# fa3d_Dock_NEW_Small.net
KiCad netlist of a schematic drawn in EAGLE
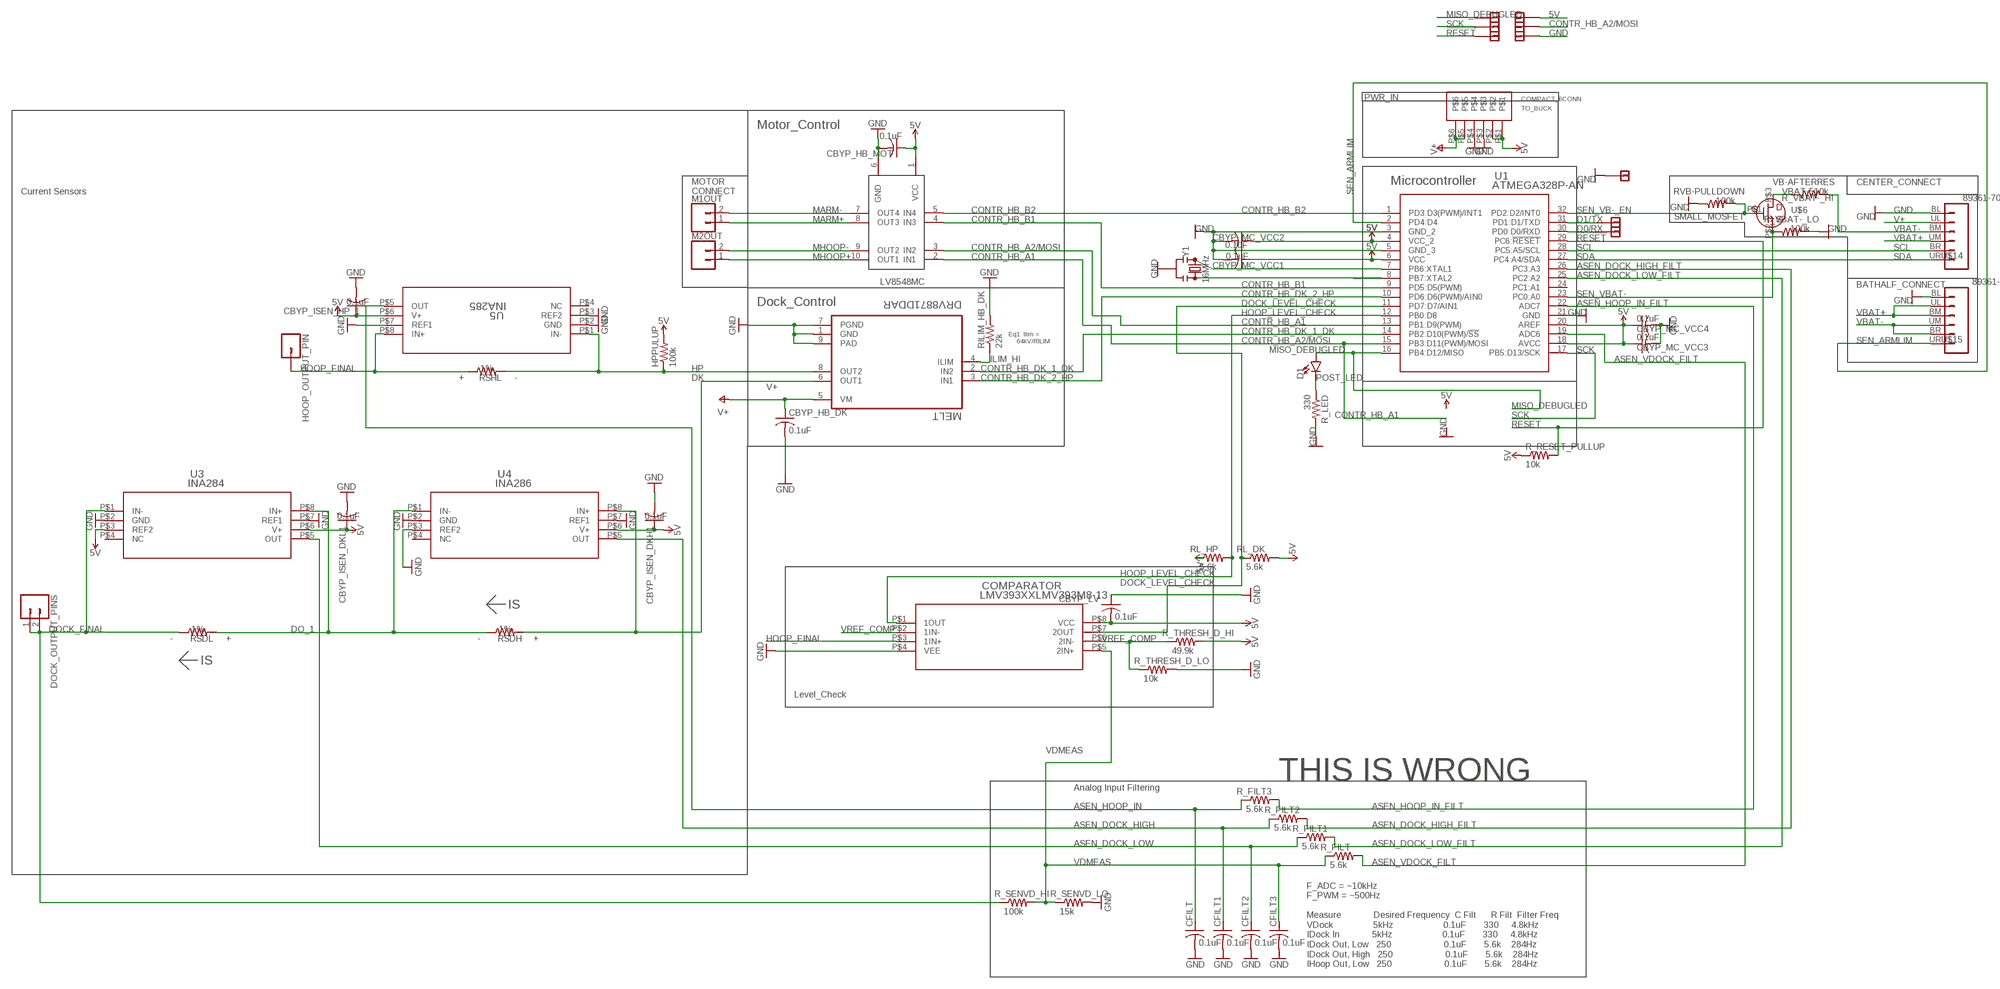
[diagram p0: schematic, sheet 1, part 1 of 2]
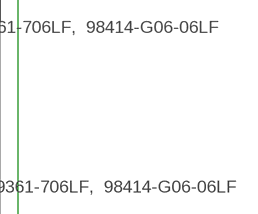
[diagram p1: schematic, sheet 1, part 2 of 2]

(export (version "E")
  (design (tool "Eeschema 10.0.6"))
  (components
    (comp (ref "CBYP_HB_DK")
      (value "0.1uF")
      (footprint "eagle-import:C0603")
      (fields (field (name "PARTNO") "CL10B104KB8NNNC"))
      (libsource (lib "eagle-import") (part "C-USC0603"))
    )
    (comp (ref "CBYP_HB_MOT")
      (value "0.1uF")
      (footprint "eagle-import:C0402")
      (fields (field (name "PARTNO") "885012105010"))
      (libsource (lib "eagle-import") (part "C-USC0402"))
    )
    (comp (ref "CBYP_ISEN_DKH1")
      (value "0.1uF")
      (footprint "eagle-import:C0402")
      (fields (field (name "PARTNO") "885012105010"))
      (libsource (lib "eagle-import") (part "C-USC0402"))
    )
    (comp (ref "CBYP_ISEN_DKL1")
      (value "0.1uF")
      (footprint "eagle-import:C0402")
      (fields (field (name "PARTNO") "885012105010"))
      (libsource (lib "eagle-import") (part "C-USC0402"))
    )
    (comp (ref "CBYP_ISEN_HP_1")
      (value "0.1uF")
      (footprint "eagle-import:C0402")
      (fields (field (name "PARTNO") "885012105010"))
      (libsource (lib "eagle-import") (part "C-USC0402"))
    )
    (comp (ref "CBYP_LV")
      (value "0.1uF")
      (footprint "eagle-import:C0402")
      (fields (field (name "PARTNO") "885012105010"))
      (libsource (lib "eagle-import") (part "C-USC0402"))
    )
    (comp (ref "CBYP_MC_VCC1")
      (value "0.1uF")
      (footprint "eagle-import:C0402")
      (fields (field (name "PARTNO") "885012105010"))
      (libsource (lib "eagle-import") (part "C-USC0402"))
    )
    (comp (ref "CBYP_MC_VCC2")
      (value "0.1uF")
      (footprint "eagle-import:C0402")
      (fields (field (name "PARTNO") "885012105010"))
      (libsource (lib "eagle-import") (part "C-USC0402"))
    )
    (comp (ref "CBYP_MC_VCC3")
      (value "0.1uF")
      (footprint "eagle-import:C0402")
      (fields (field (name "PARTNO") "885012105010"))
      (libsource (lib "eagle-import") (part "C-USC0402"))
    )
    (comp (ref "CBYP_MC_VCC4")
      (value "0.1uF")
      (footprint "eagle-import:C0402")
      (fields (field (name "PARTNO") "885012105010"))
      (libsource (lib "eagle-import") (part "C-USC0402"))
    )
    (comp (ref "CFILT")
      (value "0.1uF")
      (footprint "eagle-import:C0402")
      (fields (field (name "PARTNO") "885012105010"))
      (libsource (lib "eagle-import") (part "C-USC0402"))
    )
    (comp (ref "CFILT1")
      (value "0.1uF")
      (footprint "eagle-import:C0402")
      (fields (field (name "PARTNO") "885012105010"))
      (libsource (lib "eagle-import") (part "C-USC0402"))
    )
    (comp (ref "CFILT2")
      (value "0.1uF")
      (footprint "eagle-import:C0402")
      (fields (field (name "PARTNO") "885012105010"))
      (libsource (lib "eagle-import") (part "C-USC0402"))
    )
    (comp (ref "CFILT3")
      (value "0.1uF")
      (footprint "eagle-import:C0402")
      (fields (field (name "PARTNO") "885012105010"))
      (libsource (lib "eagle-import") (part "C-USC0402"))
    )
    (comp (ref "COMPARATOR")
      (value "LMV393XXLMV393M8-13")
      (footprint "eagle-import:MSOP-8")
      (fields (field (name "PARTNO") "LMV393M8-13"))
      (libsource (lib "eagle-import") (part "LMV393XXLMV393M8-13"))
    )
    (comp (ref "D1")
      (value "LED0603")
      (footprint "eagle-import:LED-0603")
      (fields (field (name "PARTNO") "SML-D12U1WT86"))
      (libsource (lib "eagle-import") (part "LED0603"))
    )
    (comp (ref "DOCK_OUTPUT_PINS")
      (value "CONN_02")
      (footprint "eagle-import:1X02")
      (libsource (lib "eagle-import") (part "CONN_02"))
    )
    (comp (ref "HOOP_OUTPUT_PIN")
      (value "CONN_01")
      (footprint "eagle-import:1X01")
      (libsource (lib "eagle-import") (part "CONN_01"))
    )
    (comp (ref "HPPULUP")
      (value "100k")
      (footprint "eagle-import:R0402")
      (fields (field (name "PARTNO") "RMCF0402JT100K"))
      (libsource (lib "eagle-import") (part "R-US_R0402"))
    )
    (comp (ref "M1OUT")
      (value "CONN_02")
      (footprint "eagle-import:1X02")
      (libsource (lib "eagle-import") (part "CONN_02"))
    )
    (comp (ref "M2OUT")
      (value "CONN_02")
      (footprint "eagle-import:1X02")
      (libsource (lib "eagle-import") (part "CONN_02"))
    )
    (comp (ref "MELT")
      (value "DRV8871DDAR")
      (footprint "eagle-import:SOIC127P600X170-8N")
      (fields (field (name "DIGI-KEY_PART_NUMBER") "296-43024-1-ND") (field (name "MF") "Texas Instruments"))
      (libsource (lib "eagle-import") (part "DRV8871DDAR"))
    )
    (comp (ref "MOTOR")
      (value "LV8548MC-AH")
      (footprint "eagle-import:10-SOP")
      (libsource (lib "eagle-import") (part "LV8548MC-AH"))
    )
    (comp (ref "RILIM_HB_DK")
      (value "22k")
      (footprint "eagle-import:R0603")
      (fields (field (name "PARTNO") "RMCF0402JT22K0"))
      (libsource (lib "eagle-import") (part "R-US_R0603"))
    )
    (comp (ref "RL_DK")
      (value "5.6k")
      (footprint "eagle-import:R0402")
      (fields (field (name "PARTNO") "CRGCQ0402F5K6"))
      (libsource (lib "eagle-import") (part "R-US_R0402"))
    )
    (comp (ref "RL_HP")
      (value "5.6k")
      (footprint "eagle-import:R0402")
      (fields (field (name "PARTNO") "CRGCQ0402F5K6"))
      (libsource (lib "eagle-import") (part "R-US_R0402"))
    )
    (comp (ref "RSDH")
      (value "25m")
      (footprint "eagle-import:R0603")
      (fields (field (name "PARTNO") "ERJ-3BWFR025V") (field (name "SIZE") "1206") (field (name "TOL") "1%"))
      (libsource (lib "eagle-import") (part "R-US_R0603"))
    )
    (comp (ref "RSDL")
      (value "25m")
      (footprint "eagle-import:R0603")
      (fields (field (name "PARTNO") "ERJ-3BWFR025V") (field (name "SIZE") "1206") (field (name "TOL") "1%"))
      (libsource (lib "eagle-import") (part "R-US_R0603"))
    )
    (comp (ref "RSHL")
      (value "25m")
      (footprint "eagle-import:R0603")
      (fields (field (name "PARTNO") "ERJ-3BWFR025V") (field (name "SIZE") "1206") (field (name "TOL") "1%"))
      (libsource (lib "eagle-import") (part "R-US_R0603"))
    )
    (comp (ref "RVB-PULLDOWN")
      (value "100k")
      (footprint "eagle-import:R0402")
      (fields (field (name "PARTNO") "RMCF0402JT100K"))
      (libsource (lib "eagle-import") (part "R-US_R0402"))
    )
    (comp (ref "R_FILT")
      (value "5.6k")
      (footprint "eagle-import:R0402")
      (fields (field (name "PARTNO") "CRGCQ0402F5K6"))
      (libsource (lib "eagle-import") (part "R-US_R0402"))
    )
    (comp (ref "R_FILT1")
      (value "5.6k")
      (footprint "eagle-import:R0402")
      (fields (field (name "PARTNO") "CRGCQ0402F5K6"))
      (libsource (lib "eagle-import") (part "R-US_R0402"))
    )
    (comp (ref "R_FILT2")
      (value "5.6k")
      (footprint "eagle-import:R0402")
      (fields (field (name "PARTNO") "CRGCQ0402F5K6"))
      (libsource (lib "eagle-import") (part "R-US_R0402"))
    )
    (comp (ref "R_FILT3")
      (value "5.6k")
      (footprint "eagle-import:R0402")
      (fields (field (name "PARTNO") "CRGCQ0402F5K6"))
      (libsource (lib "eagle-import") (part "R-US_R0402"))
    )
    (comp (ref "R_LED")
      (value "330")
      (footprint "eagle-import:R0402")
      (fields (field (name "PARTNO") "RMCF0402JT330R"))
      (libsource (lib "eagle-import") (part "R-US_R0402"))
    )
    (comp (ref "R_RESET_PULLUP")
      (value "10k")
      (footprint "eagle-import:R0402")
      (fields (field (name "PARTNO") "RR0510P-103-D"))
      (libsource (lib "eagle-import") (part "R-US_R0402"))
    )
    (comp (ref "R_SENVD_HI")
      (value "100k")
      (footprint "eagle-import:R0402")
      (fields (field (name "PARTNO") "RMCF0402JT100K"))
      (libsource (lib "eagle-import") (part "R-US_R0402"))
    )
    (comp (ref "R_SENVD_LO")
      (value "15k")
      (footprint "eagle-import:R0402")
      (fields (field (name "PARTNO") "RMCF0402JT15K0"))
      (libsource (lib "eagle-import") (part "R-US_R0402"))
    )
    (comp (ref "R_THRESH_D_HI")
      (value "49.9k")
      (footprint "eagle-import:R0402")
      (fields (field (name "PARTNO") "RMCF0402FT49K9"))
      (libsource (lib "eagle-import") (part "R-US_R0402"))
    )
    (comp (ref "R_THRESH_D_LO")
      (value "10k")
      (footprint "eagle-import:R0402")
      (fields (field (name "PARTNO") "RR0510P-103-D"))
      (libsource (lib "eagle-import") (part "R-US_R0402"))
    )
    (comp (ref "R_VBAT-_HI")
      (value "510k")
      (footprint "eagle-import:R0402")
      (fields (field (name "PARTNO") "RMCF0402JT510K"))
      (libsource (lib "eagle-import") (part "R-US_R0402"))
    )
    (comp (ref "R_VBAT-_LO")
      (value "100k")
      (footprint "eagle-import:R0402")
      (fields (field (name "PARTNO") "RMCF0402JT100K"))
      (libsource (lib "eagle-import") (part "R-US_R0402"))
    )
    (comp (ref "TO_BUCK")
      (value "COMPACT_6CONN")
      (footprint "eagle-import:COMPACT_6CONN")
      (libsource (lib "eagle-import") (part "COMPACT_6CONN"))
    )
    (comp (ref "U$1")
      (value "SIMPLE_VIA_CONNECTION")
      (footprint "eagle-import:SIMPLEVIA")
      (libsource (lib "eagle-import") (part "SIMPLE_VIA_CONNECTION"))
    )
    (comp (ref "U$2")
      (value "SIMPLE_VIA_CONNECTION")
      (footprint "eagle-import:SIMPLEVIA")
      (libsource (lib "eagle-import") (part "SIMPLE_VIA_CONNECTION"))
    )
    (comp (ref "U$3")
      (value "SIMPLE_VIA_CONNECTION")
      (footprint "eagle-import:SIMPLEVIA")
      (libsource (lib "eagle-import") (part "SIMPLE_VIA_CONNECTION"))
    )
    (comp (ref "U$4")
      (value "SIMPLE_VIA_CONNECTION")
      (footprint "eagle-import:SIMPLEVIA")
      (libsource (lib "eagle-import") (part "SIMPLE_VIA_CONNECTION"))
    )
    (comp (ref "U$5")
      (value "SIMPLE_VIA_CONNECTION")
      (footprint "eagle-import:SIMPLEVIA")
      (libsource (lib "eagle-import") (part "SIMPLE_VIA_CONNECTION"))
    )
    (comp (ref "U$6")
      (value "SMALL_MOSFET")
      (footprint "eagle-import:SOT-23")
      (fields (field (name "PARTNO") "BSS138"))
      (libsource (lib "eagle-import") (part "SMALL_MOSFET"))
    )
    (comp (ref "U$7")
      (value "SIMPLE_VIA_CONNECTION")
      (footprint "eagle-import:SIMPLEVIA")
      (libsource (lib "eagle-import") (part "SIMPLE_VIA_CONNECTION"))
    )
    (comp (ref "U$8")
      (value "SIMPLE_VIA_CONNECTION")
      (footprint "eagle-import:SIMPLEVIA")
      (libsource (lib "eagle-import") (part "SIMPLE_VIA_CONNECTION"))
    )
    (comp (ref "U$9")
      (value "SIMPLE_VIA_CONNECTION")
      (footprint "eagle-import:SIMPLEVIA")
      (libsource (lib "eagle-import") (part "SIMPLE_VIA_CONNECTION"))
    )
    (comp (ref "U$10")
      (value "SIMPLE_VIA_CONNECTION")
      (footprint "eagle-import:SIMPLEVIA")
      (libsource (lib "eagle-import") (part "SIMPLE_VIA_CONNECTION"))
    )
    (comp (ref "U$14")
      (value "89361-706LF, 98414-G06-06LF")
      (footprint "eagle-import:2X3_2MMPITCH")
      (fields (field (name "PARTNO") "98414-G06-06LF"))
      (libsource (lib "eagle-import") (part "CONNECTORHEADERTHROUGHHOLE6POSITION0.079{dblquote}(2.00MM)"))
    )
    (comp (ref "U$15")
      (value "89361-706LF, 98414-G06-06LF")
      (footprint "eagle-import:2X3_2MMPITCH")
      (fields (field (name "PARTNO") "98414-G06-06LF"))
      (libsource (lib "eagle-import") (part "CONNECTORHEADERTHROUGHHOLE6POSITION0.079{dblquote}(2.00MM)"))
    )
    (comp (ref "U1")
      (value "ATMEGA328P-AN")
      (footprint "eagle-import:32A")
      (fields
        (field (name "MANUFACTURER_PART_NUMBER") "ATMEGA328PAN")
        (field (name "PARTNO") "ATMEGA328P-AUR")
      )
      (libsource (lib "eagle-import") (part "ATMEGA328P-AN"))
    )
    (comp (ref "U3")
      (value "INA284")
      (footprint "eagle-import:8-VSSOP")
      (fields (field (name "PARTNO") "INA284AIDGKR"))
      (libsource (lib "eagle-import") (part "INA28XSMALL"))
    )
    (comp (ref "U4")
      (value "INA286")
      (footprint "eagle-import:8-VSSOP")
      (fields (field (name "PARTNO") "INA286AIDGKR"))
      (libsource (lib "eagle-import") (part "INA28XSMALL"))
    )
    (comp (ref "U5")
      (value "INA285")
      (footprint "eagle-import:8-VSSOP")
      (fields (field (name "PARTNO") "INA285AIDGKR"))
      (libsource (lib "eagle-import") (part "INA28XSMALL"))
    )
    (comp (ref "Y1")
      (value "16MHz")
      (footprint "eagle-import:RESONATOR-SMD-3.2X1.3")
      (fields (field (name "PARTNO") "CSTNE16M0V530000R0"))
      (libsource (lib "eagle-import") (part "RESONATOR-16MHZSMD_3.2X1.3"))
    )
  )
  (nets
    (net (code "1") (name "/ASEN_DOCK_HIGH") (class "Default")
      (node (ref "CFILT1") (pin "1") (pinfunction "1_1") (pintype "passive"))
      (node (ref "R_FILT2") (pin "1") (pinfunction "1_1") (pintype "passive"))
      (node (ref "U4") (pin "P$5") (pinfunction "OUT_P$5") (pintype "output"))
    )
    (net (code "2") (name "/ASEN_DOCK_HIGH_FILT") (class "Default")
      (node (ref "R_FILT2") (pin "2") (pinfunction "2_2") (pintype "passive"))
      (node (ref "U1") (pin "26") (pinfunction "PC3:A3_26") (pintype "bidirectional"))
    )
    (net (code "3") (name "/ASEN_DOCK_LOW") (class "Default")
      (node (ref "CFILT2") (pin "1") (pinfunction "1_1") (pintype "passive"))
      (node (ref "R_FILT1") (pin "1") (pinfunction "1_1") (pintype "passive"))
      (node (ref "U3") (pin "P$5") (pinfunction "OUT_P$5") (pintype "output"))
    )
    (net (code "4") (name "/ASEN_DOCK_LOW_FILT") (class "Default")
      (node (ref "R_FILT1") (pin "2") (pinfunction "2_2") (pintype "passive"))
      (node (ref "U1") (pin "25") (pinfunction "PC2:A2_25") (pintype "bidirectional"))
    )
    (net (code "5") (name "/ASEN_HOOP_IN") (class "Default")
      (node (ref "CFILT") (pin "1") (pinfunction "1_1") (pintype "passive"))
      (node (ref "R_FILT3") (pin "1") (pinfunction "1_1") (pintype "passive"))
      (node (ref "U5") (pin "P$5") (pinfunction "OUT_P$5") (pintype "output"))
    )
    (net (code "6") (name "/ASEN_HOOP_IN_FILT") (class "Default")
      (node (ref "R_FILT3") (pin "2") (pinfunction "2_2") (pintype "passive"))
      (node (ref "U1") (pin "22") (pinfunction "ADC7_22") (pintype "passive"))
    )
    (net (code "7") (name "/ASEN_VDOCK_FILT") (class "Default")
      (node (ref "R_FILT") (pin "2") (pinfunction "2_2") (pintype "passive"))
      (node (ref "U1") (pin "19") (pinfunction "ADC6_19") (pintype "passive"))
    )
    (net (code "8") (name "/CONTR_HB_A1") (class "Default")
      (node (ref "MOTOR") (pin "2") (pinfunction "IN1_2") (pintype "output"))
      (node (ref "U1") (pin "15") (pinfunction "PB3:D11(PWM)/MOSI_15") (pintype "bidirectional"))
    )
    (net (code "9") (name "/CONTR_HB_A2{slash}MOSI") (class "Default")
      (node (ref "MOTOR") (pin "3") (pinfunction "IN2_3") (pintype "output"))
      (node (ref "U$9") (pin "P$1") (pinfunction "1_P$1") (pintype "passive"))
      (node (ref "U1") (pin "13") (pinfunction "PB1:D9(PWM)_13") (pintype "bidirectional"))
    )
    (net (code "10") (name "/CONTR_HB_B1") (class "Default")
      (node (ref "MOTOR") (pin "4") (pinfunction "IN3_4") (pintype "output"))
      (node (ref "U1") (pin "9") (pinfunction "PD5:D5(PWM)_9") (pintype "bidirectional"))
    )
    (net (code "11") (name "/CONTR_HB_B2") (class "Default")
      (node (ref "MOTOR") (pin "5") (pinfunction "IN4_5") (pintype "output"))
      (node (ref "U1") (pin "1") (pinfunction "PD3:D3(PWM)/INT1_1") (pintype "bidirectional"))
    )
    (net (code "12") (name "/CONTR_HB_DK_1_DK") (class "Default")
      (node (ref "MELT") (pin "2") (pinfunction "IN2_2") (pintype "input"))
      (node (ref "U1") (pin "14") (pinfunction "PB2:D10(PWM)/~{SS}_14") (pintype "bidirectional"))
    )
    (net (code "13") (name "/CONTR_HB_DK_2_HP") (class "Default")
      (node (ref "MELT") (pin "3") (pinfunction "IN1_3") (pintype "input"))
      (node (ref "U1") (pin "10") (pinfunction "PD6:D6(PWM)/AIN0_10") (pintype "bidirectional"))
    )
    (net (code "14") (name "/D0{slash}RX") (class "Default")
      (node (ref "U$5") (pin "P$1") (pinfunction "1_P$1") (pintype "passive"))
      (node (ref "U1") (pin "30") (pinfunction "PD0:D0/RXD_30") (pintype "bidirectional"))
    )
    (net (code "15") (name "/D1{slash}TX") (class "Default")
      (node (ref "U$4") (pin "P$1") (pinfunction "1_P$1") (pintype "passive"))
      (node (ref "U1") (pin "31") (pinfunction "PD1:D1/TXD_31") (pintype "bidirectional"))
    )
    (net (code "16") (name "/DK") (class "Default")
      (node (ref "MELT") (pin "6") (pinfunction "OUT1_6") (pintype "output"))
      (node (ref "RSDH") (pin "2") (pinfunction "2_2") (pintype "passive"))
      (node (ref "U4") (pin "P$8") (pinfunction "IN+_P$8") (pintype "input"))
    )
    (net (code "17") (name "/DOCK_FINAL") (class "Default")
      (node (ref "DOCK_OUTPUT_PINS") (pin "1") (pinfunction "1_1") (pintype "passive"))
      (node (ref "DOCK_OUTPUT_PINS") (pin "2") (pinfunction "2_2") (pintype "passive"))
      (node (ref "RSDL") (pin "1") (pinfunction "1_1") (pintype "passive"))
      (node (ref "R_SENVD_HI") (pin "1") (pinfunction "1_1") (pintype "passive"))
      (node (ref "U3") (pin "P$1") (pinfunction "IN-_P$1") (pintype "input"))
    )
    (net (code "18") (name "/DOCK_LEVEL_CHECK") (class "Default")
      (node (ref "COMPARATOR") (pin "P$7") (pinfunction "2OUT_P$7") (pintype "output"))
      (node (ref "RL_DK") (pin "1") (pinfunction "1_1") (pintype "passive"))
      (node (ref "U1") (pin "11") (pinfunction "PD7:D7/AIN1_11") (pintype "bidirectional"))
    )
    (net (code "19") (name "/DO_1") (class "Default")
      (node (ref "RSDH") (pin "1") (pinfunction "1_1") (pintype "passive"))
      (node (ref "RSDL") (pin "2") (pinfunction "2_2") (pintype "passive"))
      (node (ref "U3") (pin "P$8") (pinfunction "IN+_P$8") (pintype "input"))
      (node (ref "U4") (pin "P$1") (pinfunction "IN-_P$1") (pintype "input"))
    )
    (net (code "20") (name "/HOOP_FINAL") (class "Default")
      (node (ref "COMPARATOR") (pin "P$3") (pinfunction "1IN+_P$3") (pintype "input"))
      (node (ref "HOOP_OUTPUT_PIN") (pin "1") (pinfunction "1_1") (pintype "passive"))
      (node (ref "RSHL") (pin "1") (pinfunction "1_1") (pintype "passive"))
      (node (ref "U5") (pin "P$8") (pinfunction "IN+_P$8") (pintype "input"))
    )
    (net (code "21") (name "/HOOP_LEVEL_CHECK") (class "Default")
      (node (ref "COMPARATOR") (pin "P$1") (pinfunction "1OUT_P$1") (pintype "output"))
      (node (ref "RL_HP") (pin "2") (pinfunction "2_2") (pintype "passive"))
      (node (ref "U1") (pin "12") (pinfunction "PB0:D8_12") (pintype "bidirectional"))
    )
    (net (code "22") (name "/HP") (class "Default")
      (node (ref "HPPULUP") (pin "1") (pinfunction "1_1") (pintype "passive"))
      (node (ref "MELT") (pin "8") (pinfunction "OUT2_8") (pintype "output"))
      (node (ref "RSHL") (pin "2") (pinfunction "2_2") (pintype "passive"))
      (node (ref "U5") (pin "P$1") (pinfunction "IN-_P$1") (pintype "input"))
    )
    (net (code "23") (name "/ILIM_HI") (class "Default")
      (node (ref "MELT") (pin "4") (pinfunction "ILIM_4") (pintype "input"))
      (node (ref "RILIM_HB_DK") (pin "1") (pinfunction "1_1") (pintype "passive"))
    )
    (net (code "24") (name "/MARM+") (class "Default")
      (node (ref "M1OUT") (pin "1") (pinfunction "1_1") (pintype "passive"))
      (node (ref "MOTOR") (pin "8") (pinfunction "OUT3_8") (pintype "output"))
    )
    (net (code "25") (name "/MARM-") (class "Default")
      (node (ref "M1OUT") (pin "2") (pinfunction "2_2") (pintype "passive"))
      (node (ref "MOTOR") (pin "7") (pinfunction "OUT4_7") (pintype "output"))
    )
    (net (code "26") (name "/MHOOP+") (class "Default")
      (node (ref "M2OUT") (pin "1") (pinfunction "1_1") (pintype "passive"))
      (node (ref "MOTOR") (pin "10") (pinfunction "OUT1_10") (pintype "output"))
    )
    (net (code "27") (name "/MHOOP-") (class "Default")
      (node (ref "M2OUT") (pin "2") (pinfunction "2_2") (pintype "passive"))
      (node (ref "MOTOR") (pin "9") (pinfunction "OUT2_9") (pintype "output"))
    )
    (net (code "28") (name "/MISO_DEBUGLED") (class "Default")
      (node (ref "D1") (pin "A") (pinfunction "A_A") (pintype "passive"))
      (node (ref "U$2") (pin "P$1") (pinfunction "1_P$1") (pintype "passive"))
      (node (ref "U1") (pin "16") (pinfunction "PB4:D12/MISO_16") (pintype "bidirectional"))
    )
    (net (code "29") (name "/POST_LED") (class "Default")
      (node (ref "D1") (pin "C") (pinfunction "C_C") (pintype "passive"))
      (node (ref "R_LED") (pin "1") (pinfunction "1_1") (pintype "passive"))
    )
    (net (code "30") (name "/SCK") (class "Default")
      (node (ref "U$3") (pin "P$1") (pinfunction "1_P$1") (pintype "passive"))
      (node (ref "U1") (pin "17") (pinfunction "PB5:D13/SCK_17") (pintype "bidirectional"))
    )
    (net (code "31") (name "/SCL") (class "Default")
      (node (ref "U$14") (pin "BR") (pinfunction "5_BR") (pintype "passive"))
      (node (ref "U1") (pin "28") (pinfunction "PC5:A5/SCL_28") (pintype "bidirectional"))
    )
    (net (code "32") (name "/SDA") (class "Default")
      (node (ref "U$14") (pin "UR") (pinfunction "6_UR") (pintype "passive"))
      (node (ref "U1") (pin "27") (pinfunction "PC4:A4/SDA_27") (pintype "bidirectional"))
    )
    (net (code "33") (name "/SEN_ARMLIM") (class "Default")
      (node (ref "U$15") (pin "UR") (pinfunction "6_UR") (pintype "passive"))
      (node (ref "U1") (pin "2") (pinfunction "PD4:D4_2") (pintype "bidirectional"))
    )
    (net (code "34") (name "/SEN_VB-_EN") (class "Default")
      (node (ref "RVB-PULLDOWN") (pin "2") (pinfunction "2_2") (pintype "passive"))
      (node (ref "U$6") (pin "P$1") (pinfunction "G_P$1") (pintype "bidirectional"))
      (node (ref "U1") (pin "32") (pinfunction "PD2:D2/INT0_32") (pintype "bidirectional"))
    )
    (net (code "35") (name "/SEN_VBAT-") (class "Default")
      (node (ref "R_VBAT-_LO") (pin "1") (pinfunction "1_1") (pintype "passive"))
      (node (ref "U$6") (pin "P$2") (pinfunction "S_P$2") (pintype "bidirectional"))
      (node (ref "U1") (pin "23") (pinfunction "PC0:A0_23") (pintype "bidirectional"))
    )
    (net (code "36") (name "/VB-AFTERRES") (class "Default")
      (node (ref "R_VBAT-_HI") (pin "1") (pinfunction "1_1") (pintype "passive"))
      (node (ref "U$6") (pin "P$3") (pinfunction "D_P$3") (pintype "bidirectional"))
    )
    (net (code "37") (name "/VBAT+") (class "Default")
      (node (ref "U$14") (pin "UM") (pinfunction "4_UM") (pintype "passive"))
      (node (ref "U$15") (pin "BM") (pinfunction "3_BM") (pintype "passive"))
      (node (ref "U$15") (pin "UL") (pinfunction "2_UL") (pintype "passive"))
    )
    (net (code "38") (name "/VBAT-") (class "Default")
      (node (ref "R_VBAT-_HI") (pin "2") (pinfunction "2_2") (pintype "passive"))
      (node (ref "U$14") (pin "BM") (pinfunction "3_BM") (pintype "passive"))
      (node (ref "U$15") (pin "BR") (pinfunction "5_BR") (pintype "passive"))
      (node (ref "U$15") (pin "UM") (pinfunction "4_UM") (pintype "passive"))
    )
    (net (code "39") (name "/VDMEAS") (class "Default")
      (node (ref "CFILT3") (pin "1") (pinfunction "1_1") (pintype "passive"))
      (node (ref "COMPARATOR") (pin "P$5") (pinfunction "2IN+_P$5") (pintype "input"))
      (node (ref "R_FILT") (pin "1") (pinfunction "1_1") (pintype "passive"))
      (node (ref "R_SENVD_HI") (pin "2") (pinfunction "2_2") (pintype "passive"))
      (node (ref "R_SENVD_LO") (pin "1") (pinfunction "1_1") (pintype "passive"))
    )
    (net (code "40") (name "/VREF_COMP") (class "Default")
      (node (ref "COMPARATOR") (pin "P$2") (pinfunction "1IN-_P$2") (pintype "input"))
      (node (ref "COMPARATOR") (pin "P$6") (pinfunction "2IN-_P$6") (pintype "input"))
      (node (ref "R_THRESH_D_HI") (pin "1") (pinfunction "1_1") (pintype "passive"))
      (node (ref "R_THRESH_D_LO") (pin "1") (pinfunction "1_1") (pintype "passive"))
    )
    (net (code "41") (name "/~{RESET}") (class "Default")
      (node (ref "R_RESET_PULLUP") (pin "2") (pinfunction "2_2") (pintype "passive"))
      (node (ref "U$7") (pin "P$1") (pinfunction "1_P$1") (pintype "passive"))
      (node (ref "U1") (pin "29") (pinfunction "PC6:~{RESET}_29") (pintype "bidirectional"))
    )
    (net (code "42") (name "5V") (class "Default")
      (node (ref "CBYP_HB_MOT") (pin "1") (pinfunction "1_1") (pintype "passive"))
      (node (ref "CBYP_ISEN_DKH1") (pin "1") (pinfunction "1_1") (pintype "passive"))
      (node (ref "CBYP_ISEN_DKL1") (pin "1") (pinfunction "1_1") (pintype "passive"))
      (node (ref "CBYP_ISEN_HP_1") (pin "1") (pinfunction "1_1") (pintype "passive"))
      (node (ref "CBYP_LV") (pin "2") (pinfunction "2_2") (pintype "passive"))
      (node (ref "CBYP_MC_VCC1") (pin "1") (pinfunction "1_1") (pintype "passive"))
      (node (ref "CBYP_MC_VCC2") (pin "1") (pinfunction "1_1") (pintype "passive"))
      (node (ref "CBYP_MC_VCC3") (pin "1") (pinfunction "1_1") (pintype "passive"))
      (node (ref "CBYP_MC_VCC4") (pin "1") (pinfunction "1_1") (pintype "passive"))
      (node (ref "COMPARATOR") (pin "P$8") (pinfunction "VCC_P$8") (pintype "power_in"))
      (node (ref "HPPULUP") (pin "2") (pinfunction "2_2") (pintype "passive"))
      (node (ref "MOTOR") (pin "1") (pinfunction "VCC_1") (pintype "output"))
      (node (ref "RL_DK") (pin "2") (pinfunction "2_2") (pintype "passive"))
      (node (ref "RL_HP") (pin "1") (pinfunction "1_1") (pintype "passive"))
      (node (ref "R_RESET_PULLUP") (pin "1") (pinfunction "1_1") (pintype "passive"))
      (node (ref "R_THRESH_D_HI") (pin "2") (pinfunction "2_2") (pintype "passive"))
      (node (ref "TO_BUCK") (pin "P$1") (pinfunction "P$1_P$1") (pintype "bidirectional"))
      (node (ref "TO_BUCK") (pin "P$2") (pinfunction "P$2_P$2") (pintype "bidirectional"))
      (node (ref "U$10") (pin "P$1") (pinfunction "1_P$1") (pintype "passive"))
      (node (ref "U1") (pin "18") (pinfunction "AVCC_18") (pintype "power_in"))
      (node (ref "U1") (pin "20") (pinfunction "AREF_20") (pintype "passive"))
      (node (ref "U1") (pin "4") (pinfunction "VCC_2_4") (pintype "power_in"))
      (node (ref "U1") (pin "6") (pinfunction "VCC_6") (pintype "power_in"))
      (node (ref "U3") (pin "P$3") (pinfunction "REF2_P$3") (pintype "passive"))
      (node (ref "U3") (pin "P$6") (pinfunction "V+_P$6") (pintype "power_in"))
      (node (ref "U4") (pin "P$6") (pinfunction "V+_P$6") (pintype "power_in"))
      (node (ref "U5") (pin "P$6") (pinfunction "V+_P$6") (pintype "power_in"))
    )
    (net (code "43") (name "GND") (class "Default")
      (node (ref "CBYP_HB_DK") (pin "2") (pinfunction "2_2") (pintype "passive"))
      (node (ref "CBYP_HB_MOT") (pin "2") (pinfunction "2_2") (pintype "passive"))
      (node (ref "CBYP_ISEN_DKH1") (pin "2") (pinfunction "2_2") (pintype "passive"))
      (node (ref "CBYP_ISEN_DKL1") (pin "2") (pinfunction "2_2") (pintype "passive"))
      (node (ref "CBYP_ISEN_HP_1") (pin "2") (pinfunction "2_2") (pintype "passive"))
      (node (ref "CBYP_LV") (pin "1") (pinfunction "1_1") (pintype "passive"))
      (node (ref "CBYP_MC_VCC1") (pin "2") (pinfunction "2_2") (pintype "passive"))
      (node (ref "CBYP_MC_VCC2") (pin "2") (pinfunction "2_2") (pintype "passive"))
      (node (ref "CBYP_MC_VCC3") (pin "2") (pinfunction "2_2") (pintype "passive"))
      (node (ref "CBYP_MC_VCC4") (pin "2") (pinfunction "2_2") (pintype "passive"))
      (node (ref "CFILT") (pin "2") (pinfunction "2_2") (pintype "passive"))
      (node (ref "CFILT1") (pin "2") (pinfunction "2_2") (pintype "passive"))
      (node (ref "CFILT2") (pin "2") (pinfunction "2_2") (pintype "passive"))
      (node (ref "CFILT3") (pin "2") (pinfunction "2_2") (pintype "passive"))
      (node (ref "COMPARATOR") (pin "P$4") (pinfunction "VEE_P$4") (pintype "power_in"))
      (node (ref "MELT") (pin "1") (pinfunction "GND_1") (pintype "power_in"))
      (node (ref "MELT") (pin "7") (pinfunction "PGND_7") (pintype "power_in"))
      (node (ref "MELT") (pin "9") (pinfunction "PAD_9") (pintype "power_in"))
      (node (ref "MOTOR") (pin "6") (pinfunction "GND_6") (pintype "output"))
      (node (ref "RILIM_HB_DK") (pin "2") (pinfunction "2_2") (pintype "passive"))
      (node (ref "RVB-PULLDOWN") (pin "1") (pinfunction "1_1") (pintype "passive"))
      (node (ref "R_LED") (pin "2") (pinfunction "2_2") (pintype "passive"))
      (node (ref "R_SENVD_LO") (pin "2") (pinfunction "2_2") (pintype "passive"))
      (node (ref "R_THRESH_D_LO") (pin "2") (pinfunction "2_2") (pintype "passive"))
      (node (ref "R_VBAT-_LO") (pin "2") (pinfunction "2_2") (pintype "passive"))
      (node (ref "TO_BUCK") (pin "P$3") (pinfunction "P$3_P$3") (pintype "bidirectional"))
      (node (ref "TO_BUCK") (pin "P$4") (pinfunction "P$4_P$4") (pintype "bidirectional"))
      (node (ref "U$1") (pin "P$1") (pinfunction "1_P$1") (pintype "passive"))
      (node (ref "U$14") (pin "BL") (pinfunction "1_BL") (pintype "passive"))
      (node (ref "U$15") (pin "BL") (pinfunction "1_BL") (pintype "passive"))
      (node (ref "U$8") (pin "P$1") (pinfunction "1_P$1") (pintype "passive"))
      (node (ref "U1") (pin "21") (pinfunction "GND_21") (pintype "power_in"))
      (node (ref "U1") (pin "3") (pinfunction "GND_2_3") (pintype "power_in"))
      (node (ref "U1") (pin "5") (pinfunction "GND_3_5") (pintype "power_in"))
      (node (ref "U3") (pin "P$2") (pinfunction "GND_P$2") (pintype "power_in"))
      (node (ref "U3") (pin "P$7") (pinfunction "REF1_P$7") (pintype "passive"))
      (node (ref "U4") (pin "P$2") (pinfunction "GND_P$2") (pintype "power_in"))
      (node (ref "U4") (pin "P$3") (pinfunction "REF2_P$3") (pintype "passive"))
      (node (ref "U4") (pin "P$7") (pinfunction "REF1_P$7") (pintype "passive"))
      (node (ref "U5") (pin "P$2") (pinfunction "GND_P$2") (pintype "power_in"))
      (node (ref "U5") (pin "P$3") (pinfunction "REF2_P$3") (pintype "passive"))
      (node (ref "U5") (pin "P$7") (pinfunction "REF1_P$7") (pintype "passive"))
      (node (ref "Y1") (pin "2") (pinfunction "2_2") (pintype "passive"))
    )
    (net (code "44") (name "Net-(U1-PB6:XTAL1)") (class "Default")
      (node (ref "U1") (pin "7") (pinfunction "PB6:XTAL1_7") (pintype "bidirectional"))
      (node (ref "Y1") (pin "1") (pinfunction "1_1") (pintype "passive"))
    )
    (net (code "45") (name "Net-(U1-PB7:XTAL2)") (class "Default")
      (node (ref "U1") (pin "8") (pinfunction "PB7:XTAL2_8") (pintype "bidirectional"))
      (node (ref "Y1") (pin "3") (pinfunction "3_3") (pintype "passive"))
    )
    (net (code "46") (name "V+") (class "Default")
      (node (ref "CBYP_HB_DK") (pin "1") (pinfunction "1_1") (pintype "passive"))
      (node (ref "MELT") (pin "5") (pinfunction "VM_5") (pintype "power_in"))
      (node (ref "TO_BUCK") (pin "P$5") (pinfunction "P$5_P$5") (pintype "bidirectional"))
      (node (ref "TO_BUCK") (pin "P$6") (pinfunction "P$6_P$6") (pintype "bidirectional"))
      (node (ref "U$14") (pin "UL") (pinfunction "2_UL") (pintype "passive"))
    )
    (net (code "47") (name "unconnected-(U1-PC1:A1-Pad24)") (class "Default")
      (node (ref "U1") (pin "24") (pinfunction "PC1:A1_24") (pintype "bidirectional"))
    )
    (net (code "48") (name "unconnected-(U3-NC-PadP$4)") (class "Default")
      (node (ref "U3") (pin "P$4") (pinfunction "NC_P$4") (pintype "passive"))
    )
    (net (code "49") (name "unconnected-(U4-NC-PadP$4)") (class "Default")
      (node (ref "U4") (pin "P$4") (pinfunction "NC_P$4") (pintype "passive"))
    )
    (net (code "50") (name "unconnected-(U5-NC-PadP$4)") (class "Default")
      (node (ref "U5") (pin "P$4") (pinfunction "NC_P$4") (pintype "passive"))
    )
  )
)
